# TIA_Schematic.net
KiCad netlist of a schematic drawn in EAGLE
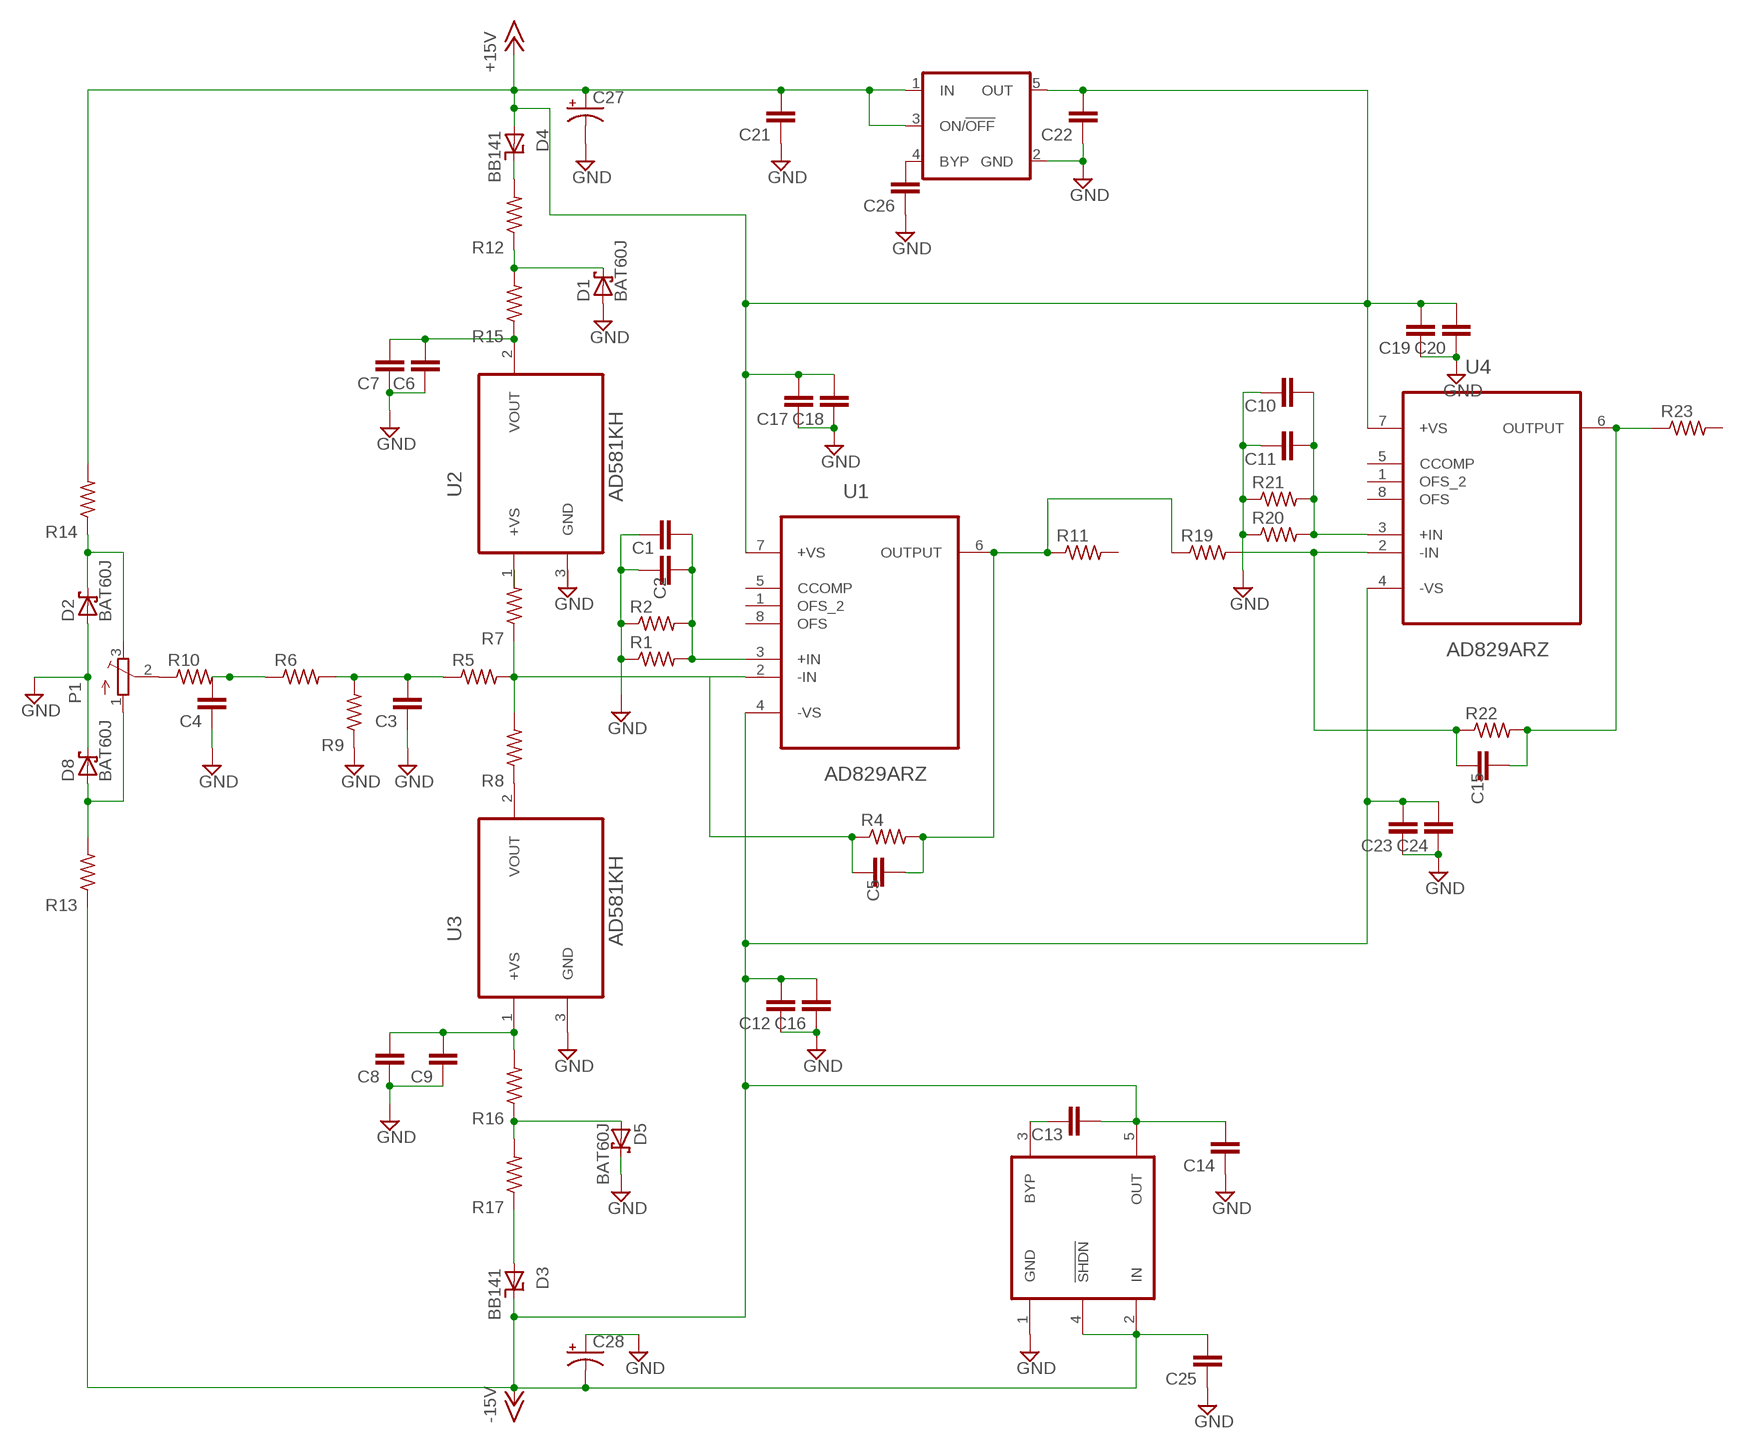
[diagram p0: schematic, sheet 1]

(export (version "E")
  (design (tool "Eeschema 10.0.6"))
  (components
    (comp (ref "C1")
      (value "C-EUC0603")
      (footprint "eagle-import:C0603")
      (libsource (lib "eagle-import") (part "C-EUC0603"))
    )
    (comp (ref "C2")
      (value "C-EUC0603")
      (footprint "eagle-import:C0603")
      (libsource (lib "eagle-import") (part "C-EUC0603"))
    )
    (comp (ref "C3")
      (value "C-EUC0603")
      (footprint "eagle-import:C0603")
      (libsource (lib "eagle-import") (part "C-EUC0603"))
    )
    (comp (ref "C4")
      (value "C-EUC0603")
      (footprint "eagle-import:C0603")
      (libsource (lib "eagle-import") (part "C-EUC0603"))
    )
    (comp (ref "C5")
      (value "C-EUC0603")
      (footprint "eagle-import:C0603")
      (libsource (lib "eagle-import") (part "C-EUC0603"))
    )
    (comp (ref "C6")
      (value "C-EUC0603")
      (footprint "eagle-import:C0603")
      (libsource (lib "eagle-import") (part "C-EUC0603"))
    )
    (comp (ref "C7")
      (value "C-EUC0603")
      (footprint "eagle-import:C0603")
      (libsource (lib "eagle-import") (part "C-EUC0603"))
    )
    (comp (ref "C8")
      (value "C-EUC0603")
      (footprint "eagle-import:C0603")
      (libsource (lib "eagle-import") (part "C-EUC0603"))
    )
    (comp (ref "C9")
      (value "C-EUC0603")
      (footprint "eagle-import:C0603")
      (libsource (lib "eagle-import") (part "C-EUC0603"))
    )
    (comp (ref "C10")
      (value "C-EUC0603")
      (footprint "eagle-import:C0603")
      (libsource (lib "eagle-import") (part "C-EUC0603"))
    )
    (comp (ref "C11")
      (value "C-EUC0603")
      (footprint "eagle-import:C0603")
      (libsource (lib "eagle-import") (part "C-EUC0603"))
    )
    (comp (ref "C12")
      (value "C-EUC0603")
      (footprint "eagle-import:C0603")
      (libsource (lib "eagle-import") (part "C-EUC0603"))
    )
    (comp (ref "C13")
      (value "C-EUC0603")
      (footprint "eagle-import:C0603")
      (libsource (lib "eagle-import") (part "C-EUC0603"))
    )
    (comp (ref "C14")
      (value "C-EUC0603")
      (footprint "eagle-import:C0603")
      (libsource (lib "eagle-import") (part "C-EUC0603"))
    )
    (comp (ref "C15")
      (value "C-EUC0603")
      (footprint "eagle-import:C0603")
      (libsource (lib "eagle-import") (part "C-EUC0603"))
    )
    (comp (ref "C16")
      (value "C-EUC0603")
      (footprint "eagle-import:C0603")
      (libsource (lib "eagle-import") (part "C-EUC0603"))
    )
    (comp (ref "C17")
      (value "C-EUC0603")
      (footprint "eagle-import:C0603")
      (libsource (lib "eagle-import") (part "C-EUC0603"))
    )
    (comp (ref "C18")
      (value "C-EUC0603")
      (footprint "eagle-import:C0603")
      (libsource (lib "eagle-import") (part "C-EUC0603"))
    )
    (comp (ref "C19")
      (value "C-EUC0603")
      (footprint "eagle-import:C0603")
      (libsource (lib "eagle-import") (part "C-EUC0603"))
    )
    (comp (ref "C20")
      (value "C-EUC0603")
      (footprint "eagle-import:C0603")
      (libsource (lib "eagle-import") (part "C-EUC0603"))
    )
    (comp (ref "C21")
      (value "C-EUC0603")
      (footprint "eagle-import:C0603")
      (libsource (lib "eagle-import") (part "C-EUC0603"))
    )
    (comp (ref "C22")
      (value "C-EUC0603")
      (footprint "eagle-import:C0603")
      (libsource (lib "eagle-import") (part "C-EUC0603"))
    )
    (comp (ref "C23")
      (value "C-EUC0603")
      (footprint "eagle-import:C0603")
      (libsource (lib "eagle-import") (part "C-EUC0603"))
    )
    (comp (ref "C24")
      (value "C-EUC0603")
      (footprint "eagle-import:C0603")
      (libsource (lib "eagle-import") (part "C-EUC0603"))
    )
    (comp (ref "C25")
      (value "C-EUC0603")
      (footprint "eagle-import:C0603")
      (libsource (lib "eagle-import") (part "C-EUC0603"))
    )
    (comp (ref "C26")
      (value "C-EUC0603")
      (footprint "eagle-import:C0603")
      (libsource (lib "eagle-import") (part "C-EUC0603"))
    )
    (comp (ref "C27")
      (value "CPOL-USETR3")
      (footprint "eagle-import:ETR3")
      (libsource (lib "eagle-import") (part "CPOL-USETR3"))
    )
    (comp (ref "C28")
      (value "CPOL-USETR3")
      (footprint "eagle-import:ETR3")
      (libsource (lib "eagle-import") (part "CPOL-USETR3"))
    )
    (comp (ref "D1")
      (value "BAT60J")
      (footprint "eagle-import:SOD323_ST")
      (libsource (lib "eagle-import") (part "BAT60J"))
    )
    (comp (ref "D2")
      (value "BAT60J")
      (footprint "eagle-import:SOD323_ST")
      (libsource (lib "eagle-import") (part "BAT60J"))
    )
    (comp (ref "D3")
      (value "BB141")
      (footprint "eagle-import:SOD523")
      (libsource (lib "eagle-import") (part "BB141"))
    )
    (comp (ref "D4")
      (value "BB141")
      (footprint "eagle-import:SOD523")
      (libsource (lib "eagle-import") (part "BB141"))
    )
    (comp (ref "D5")
      (value "BAT60J")
      (footprint "eagle-import:SOD323_ST")
      (libsource (lib "eagle-import") (part "BAT60J"))
    )
    (comp (ref "D8")
      (value "BAT60J")
      (footprint "eagle-import:SOD323_ST")
      (libsource (lib "eagle-import") (part "BAT60J"))
    )
    (comp (ref "P1")
      (value "TRIM_EU-3223G")
      (footprint "eagle-import:3223G")
      (libsource (lib "eagle-import") (part "TRIM_EU-3223G"))
    )
    (comp (ref "R1")
      (value "R-US_R0603")
      (footprint "eagle-import:R0603")
      (libsource (lib "eagle-import") (part "R-US_R0603"))
    )
    (comp (ref "R2")
      (value "R-US_R0603")
      (footprint "eagle-import:R0603")
      (libsource (lib "eagle-import") (part "R-US_R0603"))
    )
    (comp (ref "R4")
      (value "R-US_R0603")
      (footprint "eagle-import:R0603")
      (libsource (lib "eagle-import") (part "R-US_R0603"))
    )
    (comp (ref "R5")
      (value "R-US_R0603")
      (footprint "eagle-import:R0603")
      (libsource (lib "eagle-import") (part "R-US_R0603"))
    )
    (comp (ref "R6")
      (value "R-US_R0603")
      (footprint "eagle-import:R0603")
      (libsource (lib "eagle-import") (part "R-US_R0603"))
    )
    (comp (ref "R7")
      (value "R-US_R0603")
      (footprint "eagle-import:R0603")
      (libsource (lib "eagle-import") (part "R-US_R0603"))
    )
    (comp (ref "R8")
      (value "R-US_R0603")
      (footprint "eagle-import:R0603")
      (libsource (lib "eagle-import") (part "R-US_R0603"))
    )
    (comp (ref "R9")
      (value "R-US_R0603")
      (footprint "eagle-import:R0603")
      (libsource (lib "eagle-import") (part "R-US_R0603"))
    )
    (comp (ref "R10")
      (value "R-US_R0603")
      (footprint "eagle-import:R0603")
      (libsource (lib "eagle-import") (part "R-US_R0603"))
    )
    (comp (ref "R11")
      (value "R-US_R0603")
      (footprint "eagle-import:R0603")
      (libsource (lib "eagle-import") (part "R-US_R0603"))
    )
    (comp (ref "R12")
      (value "R-US_R0603")
      (footprint "eagle-import:R0603")
      (libsource (lib "eagle-import") (part "R-US_R0603"))
    )
    (comp (ref "R13")
      (value "R-US_R0603")
      (footprint "eagle-import:R0603")
      (libsource (lib "eagle-import") (part "R-US_R0603"))
    )
    (comp (ref "R14")
      (value "R-US_R0603")
      (footprint "eagle-import:R0603")
      (libsource (lib "eagle-import") (part "R-US_R0603"))
    )
    (comp (ref "R15")
      (value "R-US_R0603")
      (footprint "eagle-import:R0603")
      (libsource (lib "eagle-import") (part "R-US_R0603"))
    )
    (comp (ref "R16")
      (value "R-US_R0603")
      (footprint "eagle-import:R0603")
      (libsource (lib "eagle-import") (part "R-US_R0603"))
    )
    (comp (ref "R17")
      (value "R-US_R0603")
      (footprint "eagle-import:R0603")
      (libsource (lib "eagle-import") (part "R-US_R0603"))
    )
    (comp (ref "R19")
      (value "R-US_R0603")
      (footprint "eagle-import:R0603")
      (libsource (lib "eagle-import") (part "R-US_R0603"))
    )
    (comp (ref "R20")
      (value "R-US_R0603")
      (footprint "eagle-import:R0603")
      (libsource (lib "eagle-import") (part "R-US_R0603"))
    )
    (comp (ref "R21")
      (value "R-US_R0603")
      (footprint "eagle-import:R0603")
      (libsource (lib "eagle-import") (part "R-US_R0603"))
    )
    (comp (ref "R22")
      (value "R-US_R0603")
      (footprint "eagle-import:R0603")
      (libsource (lib "eagle-import") (part "R-US_R0603"))
    )
    (comp (ref "R23")
      (value "R-US_R0603")
      (footprint "eagle-import:R0603")
      (libsource (lib "eagle-import") (part "R-US_R0603"))
    )
    (comp (ref "U1")
      (value "AD829ARZ")
      (footprint "eagle-import:SOIC127P600X175-8N")
      (libsource (lib "eagle-import") (part "AD829ARZ"))
    )
    (comp (ref "U2")
      (value "AD581KH")
      (footprint "eagle-import:TO254P939X470-3P")
      (libsource (lib "eagle-import") (part "AD581KH"))
    )
    (comp (ref "U3")
      (value "AD581KH")
      (footprint "eagle-import:TO254P939X470-3P")
      (libsource (lib "eagle-import") (part "AD581KH"))
    )
    (comp (ref "U4")
      (value "AD829ARZ")
      (footprint "eagle-import:SOIC127P600X175-8N")
      (libsource (lib "eagle-import") (part "AD829ARZ"))
    )
    (comp (ref "U7")
      (value "LP2992M5")
      (footprint "eagle-import:SOT23-5")
      (libsource (lib "eagle-import") (part "LP2992M5"))
    )
    (comp (ref "U8")
      (value "LT1964")
      (footprint "eagle-import:SOT23-5")
      (libsource (lib "eagle-import") (part "LT1964"))
    )
  )
  (nets
    (net (code "1") (name "+15V") (class "Default")
      (node (ref "C17") (pin "2") (pinfunction "2_2") (pintype "passive"))
      (node (ref "C18") (pin "2") (pinfunction "2_2") (pintype "passive"))
      (node (ref "C19") (pin "2") (pinfunction "2_2") (pintype "passive"))
      (node (ref "C20") (pin "2") (pinfunction "2_2") (pintype "passive"))
      (node (ref "C21") (pin "2") (pinfunction "2_2") (pintype "passive"))
      (node (ref "C22") (pin "2") (pinfunction "2_2") (pintype "passive"))
      (node (ref "C27") (pin "+") (pinfunction "+_+") (pintype "passive"))
      (node (ref "D4") (pin "A") (pinfunction "A_A") (pintype "passive"))
      (node (ref "R14") (pin "2") (pinfunction "2_2") (pintype "passive"))
      (node (ref "U1") (pin "7") (pinfunction "+VS_7") (pintype "power_in"))
      (node (ref "U4") (pin "7") (pinfunction "+VS_7") (pintype "power_in"))
      (node (ref "U7") (pin "1") (pinfunction "IN_1") (pintype "input"))
      (node (ref "U7") (pin "3") (pinfunction "ON/~{OFF}_3") (pintype "input"))
      (node (ref "U7") (pin "5") (pinfunction "OUT_5") (pintype "passive"))
    )
    (net (code "2") (name "-15V") (class "Default")
      (node (ref "C12") (pin "2") (pinfunction "2_2") (pintype "passive"))
      (node (ref "C13") (pin "2") (pinfunction "2_2") (pintype "passive"))
      (node (ref "C14") (pin "2") (pinfunction "2_2") (pintype "passive"))
      (node (ref "C16") (pin "2") (pinfunction "2_2") (pintype "passive"))
      (node (ref "C23") (pin "2") (pinfunction "2_2") (pintype "passive"))
      (node (ref "C24") (pin "2") (pinfunction "2_2") (pintype "passive"))
      (node (ref "C25") (pin "2") (pinfunction "2_2") (pintype "passive"))
      (node (ref "C28") (pin "-") (pinfunction "-_-") (pintype "passive"))
      (node (ref "D3") (pin "C") (pinfunction "C_C") (pintype "passive"))
      (node (ref "R13") (pin "1") (pinfunction "1_1") (pintype "passive"))
      (node (ref "U1") (pin "4") (pinfunction "-VS_4") (pintype "power_in"))
      (node (ref "U4") (pin "4") (pinfunction "-VS_4") (pintype "power_in"))
      (node (ref "U8") (pin "2") (pinfunction "IN_2") (pintype "bidirectional"))
      (node (ref "U8") (pin "4") (pinfunction "~{SHDN}_4") (pintype "bidirectional"))
      (node (ref "U8") (pin "5") (pinfunction "OUT_5") (pintype "bidirectional"))
    )
    (net (code "3") (name "GND") (class "Default")
      (node (ref "C1") (pin "1") (pinfunction "1_1") (pintype "passive"))
      (node (ref "C10") (pin "1") (pinfunction "1_1") (pintype "passive"))
      (node (ref "C11") (pin "1") (pinfunction "1_1") (pintype "passive"))
      (node (ref "C12") (pin "1") (pinfunction "1_1") (pintype "passive"))
      (node (ref "C14") (pin "1") (pinfunction "1_1") (pintype "passive"))
      (node (ref "C16") (pin "1") (pinfunction "1_1") (pintype "passive"))
      (node (ref "C17") (pin "1") (pinfunction "1_1") (pintype "passive"))
      (node (ref "C18") (pin "1") (pinfunction "1_1") (pintype "passive"))
      (node (ref "C19") (pin "1") (pinfunction "1_1") (pintype "passive"))
      (node (ref "C2") (pin "1") (pinfunction "1_1") (pintype "passive"))
      (node (ref "C20") (pin "1") (pinfunction "1_1") (pintype "passive"))
      (node (ref "C21") (pin "1") (pinfunction "1_1") (pintype "passive"))
      (node (ref "C22") (pin "1") (pinfunction "1_1") (pintype "passive"))
      (node (ref "C23") (pin "1") (pinfunction "1_1") (pintype "passive"))
      (node (ref "C24") (pin "1") (pinfunction "1_1") (pintype "passive"))
      (node (ref "C25") (pin "1") (pinfunction "1_1") (pintype "passive"))
      (node (ref "C26") (pin "1") (pinfunction "1_1") (pintype "passive"))
      (node (ref "C27") (pin "-") (pinfunction "-_-") (pintype "passive"))
      (node (ref "C28") (pin "+") (pinfunction "+_+") (pintype "passive"))
      (node (ref "C3") (pin "1") (pinfunction "1_1") (pintype "passive"))
      (node (ref "C4") (pin "1") (pinfunction "1_1") (pintype "passive"))
      (node (ref "C6") (pin "1") (pinfunction "1_1") (pintype "passive"))
      (node (ref "C7") (pin "1") (pinfunction "1_1") (pintype "passive"))
      (node (ref "C8") (pin "1") (pinfunction "1_1") (pintype "passive"))
      (node (ref "C9") (pin "1") (pinfunction "1_1") (pintype "passive"))
      (node (ref "D1") (pin "A") (pinfunction "A_A") (pintype "passive"))
      (node (ref "D2") (pin "A") (pinfunction "A_A") (pintype "passive"))
      (node (ref "D5") (pin "C") (pinfunction "C_C") (pintype "passive"))
      (node (ref "D8") (pin "C") (pinfunction "C_C") (pintype "passive"))
      (node (ref "R1") (pin "1") (pinfunction "1_1") (pintype "passive"))
      (node (ref "R2") (pin "1") (pinfunction "1_1") (pintype "passive"))
      (node (ref "R20") (pin "1") (pinfunction "1_1") (pintype "passive"))
      (node (ref "R21") (pin "1") (pinfunction "1_1") (pintype "passive"))
      (node (ref "R9") (pin "1") (pinfunction "1_1") (pintype "passive"))
      (node (ref "U2") (pin "3") (pinfunction "GND_3") (pintype "passive"))
      (node (ref "U3") (pin "3") (pinfunction "GND_3") (pintype "passive"))
      (node (ref "U7") (pin "2") (pinfunction "GND_2") (pintype "power_in"))
      (node (ref "U8") (pin "1") (pinfunction "GND_1") (pintype "bidirectional"))
    )
    (net (code "4") (name "Net-(C3-Pad2)") (class "Default")
      (node (ref "C3") (pin "2") (pinfunction "2_2") (pintype "passive"))
      (node (ref "R5") (pin "1") (pinfunction "1_1") (pintype "passive"))
      (node (ref "R6") (pin "2") (pinfunction "2_2") (pintype "passive"))
      (node (ref "R9") (pin "2") (pinfunction "2_2") (pintype "passive"))
    )
    (net (code "5") (name "Net-(C4-Pad2)") (class "Default")
      (node (ref "C4") (pin "2") (pinfunction "2_2") (pintype "passive"))
      (node (ref "R10") (pin "2") (pinfunction "2_2") (pintype "passive"))
      (node (ref "R6") (pin "1") (pinfunction "1_1") (pintype "passive"))
    )
    (net (code "6") (name "Net-(D1-PadC)") (class "Default")
      (node (ref "D1") (pin "C") (pinfunction "C_C") (pintype "passive"))
      (node (ref "R12") (pin "1") (pinfunction "1_1") (pintype "passive"))
      (node (ref "R15") (pin "2") (pinfunction "2_2") (pintype "passive"))
    )
    (net (code "7") (name "Net-(D3-PadA)") (class "Default")
      (node (ref "D3") (pin "A") (pinfunction "A_A") (pintype "passive"))
      (node (ref "R17") (pin "1") (pinfunction "1_1") (pintype "passive"))
    )
    (net (code "8") (name "Net-(D4-PadC)") (class "Default")
      (node (ref "D4") (pin "C") (pinfunction "C_C") (pintype "passive"))
      (node (ref "R12") (pin "2") (pinfunction "2_2") (pintype "passive"))
    )
    (net (code "9") (name "Net-(D5-PadA)") (class "Default")
      (node (ref "D5") (pin "A") (pinfunction "A_A") (pintype "passive"))
      (node (ref "R16") (pin "1") (pinfunction "1_1") (pintype "passive"))
      (node (ref "R17") (pin "2") (pinfunction "2_2") (pintype "passive"))
    )
    (net (code "10") (name "Net-(P1-A)") (class "Default")
      (node (ref "D8") (pin "A") (pinfunction "A_A") (pintype "passive"))
      (node (ref "P1") (pin "1") (pinfunction "A_1") (pintype "passive"))
      (node (ref "R13") (pin "2") (pinfunction "2_2") (pintype "passive"))
    )
    (net (code "11") (name "Net-(P1-E)") (class "Default")
      (node (ref "D2") (pin "C") (pinfunction "C_C") (pintype "passive"))
      (node (ref "P1") (pin "3") (pinfunction "E_3") (pintype "passive"))
      (node (ref "R14") (pin "1") (pinfunction "1_1") (pintype "passive"))
    )
    (net (code "12") (name "Net-(P1-S)") (class "Default")
      (node (ref "P1") (pin "2") (pinfunction "S_2") (pintype "passive"))
      (node (ref "R10") (pin "1") (pinfunction "1_1") (pintype "passive"))
    )
    (net (code "13") (name "Net-(U1-+IN)") (class "Default")
      (node (ref "C1") (pin "2") (pinfunction "2_2") (pintype "passive"))
      (node (ref "C2") (pin "2") (pinfunction "2_2") (pintype "passive"))
      (node (ref "R1") (pin "2") (pinfunction "2_2") (pintype "passive"))
      (node (ref "R2") (pin "2") (pinfunction "2_2") (pintype "passive"))
      (node (ref "U1") (pin "3") (pinfunction "+IN_3") (pintype "input"))
    )
    (net (code "14") (name "Net-(U1--IN)") (class "Default")
      (node (ref "C5") (pin "1") (pinfunction "1_1") (pintype "passive"))
      (node (ref "R4") (pin "1") (pinfunction "1_1") (pintype "passive"))
      (node (ref "R5") (pin "2") (pinfunction "2_2") (pintype "passive"))
      (node (ref "R7") (pin "1") (pinfunction "1_1") (pintype "passive"))
      (node (ref "R8") (pin "2") (pinfunction "2_2") (pintype "passive"))
      (node (ref "U1") (pin "2") (pinfunction "-IN_2") (pintype "input"))
    )
    (net (code "15") (name "Net-(U1-OUTPUT)") (class "Default")
      (node (ref "C5") (pin "2") (pinfunction "2_2") (pintype "passive"))
      (node (ref "R11") (pin "1") (pinfunction "1_1") (pintype "passive"))
      (node (ref "R19") (pin "1") (pinfunction "1_1") (pintype "passive"))
      (node (ref "R4") (pin "2") (pinfunction "2_2") (pintype "passive"))
      (node (ref "U1") (pin "6") (pinfunction "OUTPUT_6") (pintype "output"))
    )
    (net (code "16") (name "Net-(U2-+VS)") (class "Default")
      (node (ref "R7") (pin "2") (pinfunction "2_2") (pintype "passive"))
      (node (ref "U2") (pin "1") (pinfunction "+VS_1") (pintype "power_in"))
    )
    (net (code "17") (name "Net-(U2-VOUT)") (class "Default")
      (node (ref "C6") (pin "2") (pinfunction "2_2") (pintype "passive"))
      (node (ref "C7") (pin "2") (pinfunction "2_2") (pintype "passive"))
      (node (ref "R15") (pin "1") (pinfunction "1_1") (pintype "passive"))
      (node (ref "U2") (pin "2") (pinfunction "VOUT_2") (pintype "output"))
    )
    (net (code "18") (name "Net-(U3-+VS)") (class "Default")
      (node (ref "C8") (pin "2") (pinfunction "2_2") (pintype "passive"))
      (node (ref "C9") (pin "2") (pinfunction "2_2") (pintype "passive"))
      (node (ref "R16") (pin "2") (pinfunction "2_2") (pintype "passive"))
      (node (ref "U3") (pin "1") (pinfunction "+VS_1") (pintype "power_in"))
    )
    (net (code "19") (name "Net-(U3-VOUT)") (class "Default")
      (node (ref "R8") (pin "1") (pinfunction "1_1") (pintype "passive"))
      (node (ref "U3") (pin "2") (pinfunction "VOUT_2") (pintype "output"))
    )
    (net (code "20") (name "Net-(U4-+IN)") (class "Default")
      (node (ref "C10") (pin "2") (pinfunction "2_2") (pintype "passive"))
      (node (ref "C11") (pin "2") (pinfunction "2_2") (pintype "passive"))
      (node (ref "R20") (pin "2") (pinfunction "2_2") (pintype "passive"))
      (node (ref "R21") (pin "2") (pinfunction "2_2") (pintype "passive"))
      (node (ref "U4") (pin "3") (pinfunction "+IN_3") (pintype "input"))
    )
    (net (code "21") (name "Net-(U4--IN)") (class "Default")
      (node (ref "C15") (pin "1") (pinfunction "1_1") (pintype "passive"))
      (node (ref "R19") (pin "2") (pinfunction "2_2") (pintype "passive"))
      (node (ref "R22") (pin "1") (pinfunction "1_1") (pintype "passive"))
      (node (ref "U4") (pin "2") (pinfunction "-IN_2") (pintype "input"))
    )
    (net (code "22") (name "Net-(U4-OUTPUT)") (class "Default")
      (node (ref "C15") (pin "2") (pinfunction "2_2") (pintype "passive"))
      (node (ref "R22") (pin "2") (pinfunction "2_2") (pintype "passive"))
      (node (ref "R23") (pin "1") (pinfunction "1_1") (pintype "passive"))
      (node (ref "U4") (pin "6") (pinfunction "OUTPUT_6") (pintype "output"))
    )
    (net (code "23") (name "Net-(U7-BYP)") (class "Default")
      (node (ref "C26") (pin "2") (pinfunction "2_2") (pintype "passive"))
      (node (ref "U7") (pin "4") (pinfunction "BYP_4") (pintype "passive"))
    )
    (net (code "24") (name "Net-(U8-BYP)") (class "Default")
      (node (ref "C13") (pin "1") (pinfunction "1_1") (pintype "passive"))
      (node (ref "U8") (pin "3") (pinfunction "BYP_3") (pintype "bidirectional"))
    )
    (net (code "25") (name "unconnected-(R11-Pad2)") (class "Default")
      (node (ref "R11") (pin "2") (pinfunction "2_2") (pintype "passive"))
    )
    (net (code "26") (name "unconnected-(R23-Pad2)") (class "Default")
      (node (ref "R23") (pin "2") (pinfunction "2_2") (pintype "passive"))
    )
    (net (code "27") (name "unconnected-(U1-CCOMP-Pad5)") (class "Default")
      (node (ref "U1") (pin "5") (pinfunction "CCOMP_5") (pintype "passive"))
    )
    (net (code "28") (name "unconnected-(U1-OFS-Pad8)") (class "Default")
      (node (ref "U1") (pin "8") (pinfunction "OFS_8") (pintype "passive"))
    )
    (net (code "29") (name "unconnected-(U1-OFS_2-Pad1)") (class "Default")
      (node (ref "U1") (pin "1") (pinfunction "OFS_2_1") (pintype "passive"))
    )
    (net (code "30") (name "unconnected-(U4-CCOMP-Pad5)") (class "Default")
      (node (ref "U4") (pin "5") (pinfunction "CCOMP_5") (pintype "passive"))
    )
    (net (code "31") (name "unconnected-(U4-OFS-Pad8)") (class "Default")
      (node (ref "U4") (pin "8") (pinfunction "OFS_8") (pintype "passive"))
    )
    (net (code "32") (name "unconnected-(U4-OFS_2-Pad1)") (class "Default")
      (node (ref "U4") (pin "1") (pinfunction "OFS_2_1") (pintype "passive"))
    )
  )
)
